# stl_mainboard.net
KiCad netlist of a schematic drawn in EAGLE
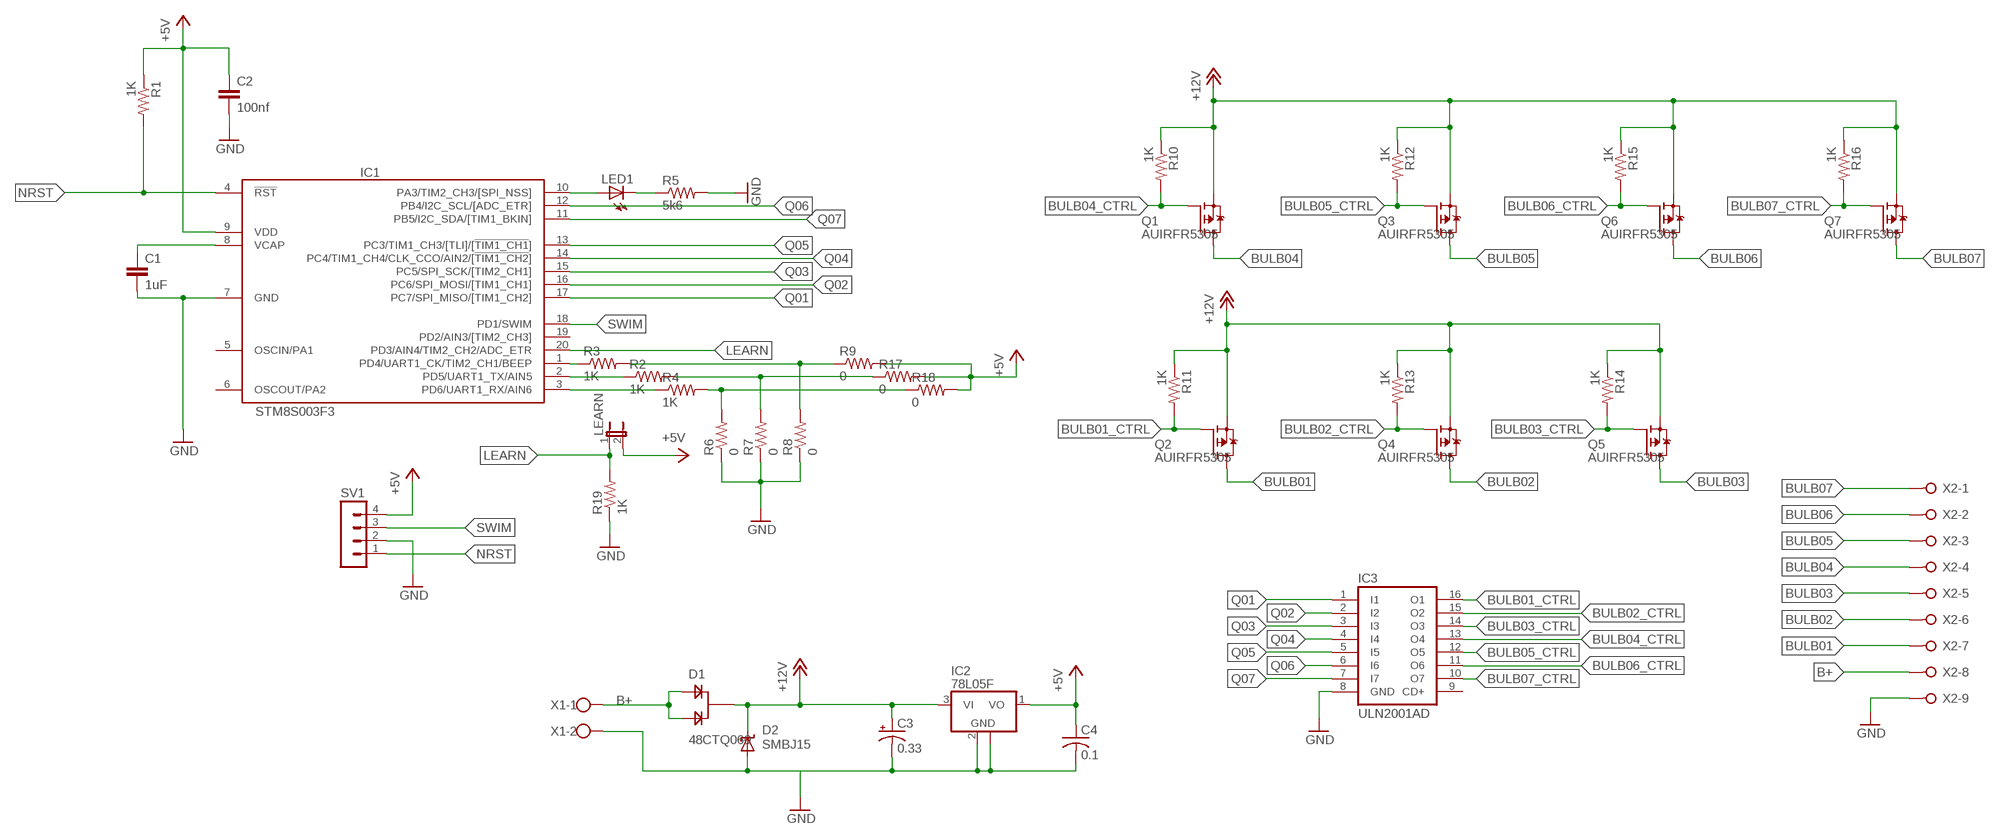
[diagram p0: schematic, sheet 1]

(export (version "E")
  (design (tool "Eeschema 10.0.6"))
  (components
    (comp (ref "C1")
      (value "1uF")
      (footprint "eagle-import:C1206")
      (libsource (lib "eagle-import") (part "C-EUC1206"))
    )
    (comp (ref "C2")
      (value "100nf")
      (footprint "eagle-import:C1206")
      (libsource (lib "eagle-import") (part "C-EUC1206"))
    )
    (comp (ref "C3")
      (value "0.33")
      (footprint "eagle-import:E5-8,5")
      (libsource (lib "eagle-import") (part "CPOL-USE5-8.5"))
    )
    (comp (ref "C4")
      (value "0.1")
      (footprint "eagle-import:C0805")
      (libsource (lib "eagle-import") (part "C-USC0805"))
    )
    (comp (ref "D1")
      (value "48CTQ060")
      (footprint "eagle-import:TO263AB")
      (libsource (lib "eagle-import") (part "48CTQ060"))
    )
    (comp (ref "D2")
      (value "SMBJ15")
      (footprint "eagle-import:SMBJ")
      (libsource (lib "eagle-import") (part "SUPPRESSOR-SMBJ"))
    )
    (comp (ref "IC1")
      (value "STM8S003F3")
      (footprint "eagle-import:TSSOP20")
      (libsource (lib "eagle-import") (part "STM8S003F3"))
    )
    (comp (ref "IC2")
      (value "78L05F")
      (footprint "eagle-import:SOT89")
      (libsource (lib "eagle-import") (part "78LF05"))
    )
    (comp (ref "IC3")
      (value "ULN2001AD")
      (footprint "eagle-import:SO16")
      (libsource (lib "eagle-import") (part "ULN2001AD"))
    )
    (comp (ref "LEARN")
      (value "JP1E")
      (footprint "eagle-import:JP1")
      (libsource (lib "eagle-import") (part "JP1E"))
    )
    (comp (ref "LED1")
      (value "LEDSML1206")
      (footprint "eagle-import:SML1206")
      (libsource (lib "eagle-import") (part "LEDSML1206"))
    )
    (comp (ref "Q1")
      (value "AUIRFR5305")
      (footprint "eagle-import:TO252")
      (libsource (lib "eagle-import") (part "SPD30P06PTO252"))
    )
    (comp (ref "Q2")
      (value "AUIRFR5305")
      (footprint "eagle-import:TO252")
      (libsource (lib "eagle-import") (part "SPD30P06PTO252"))
    )
    (comp (ref "Q3")
      (value "AUIRFR5305")
      (footprint "eagle-import:TO252")
      (libsource (lib "eagle-import") (part "SPD30P06PTO252"))
    )
    (comp (ref "Q4")
      (value "AUIRFR5305")
      (footprint "eagle-import:TO252")
      (libsource (lib "eagle-import") (part "SPD30P06PTO252"))
    )
    (comp (ref "Q5")
      (value "AUIRFR5305")
      (footprint "eagle-import:TO252")
      (libsource (lib "eagle-import") (part "SPD30P06PTO252"))
    )
    (comp (ref "Q6")
      (value "AUIRFR5305")
      (footprint "eagle-import:TO252")
      (libsource (lib "eagle-import") (part "SPD30P06PTO252"))
    )
    (comp (ref "Q7")
      (value "AUIRFR5305")
      (footprint "eagle-import:TO252")
      (libsource (lib "eagle-import") (part "SPD30P06PTO252"))
    )
    (comp (ref "R1")
      (value "1K")
      (footprint "eagle-import:M0805")
      (libsource (lib "eagle-import") (part "R-US_M0805"))
    )
    (comp (ref "R2")
      (value "1K")
      (footprint "eagle-import:M0805")
      (libsource (lib "eagle-import") (part "R-US_M0805"))
    )
    (comp (ref "R3")
      (value "1K")
      (footprint "eagle-import:M0805")
      (libsource (lib "eagle-import") (part "R-US_M0805"))
    )
    (comp (ref "R4")
      (value "1K")
      (footprint "eagle-import:M0805")
      (libsource (lib "eagle-import") (part "R-US_M0805"))
    )
    (comp (ref "R5")
      (value "5k6")
      (footprint "eagle-import:M0805")
      (libsource (lib "eagle-import") (part "R-US_M0805"))
    )
    (comp (ref "R6")
      (value "0")
      (footprint "eagle-import:M0805")
      (libsource (lib "eagle-import") (part "R-US_M0805"))
    )
    (comp (ref "R7")
      (value "0")
      (footprint "eagle-import:M0805")
      (libsource (lib "eagle-import") (part "R-US_M0805"))
    )
    (comp (ref "R8")
      (value "0")
      (footprint "eagle-import:M0805")
      (libsource (lib "eagle-import") (part "R-US_M0805"))
    )
    (comp (ref "R9")
      (value "0")
      (footprint "eagle-import:M0805")
      (libsource (lib "eagle-import") (part "R-US_M0805"))
    )
    (comp (ref "R10")
      (value "1K")
      (footprint "eagle-import:M0805")
      (libsource (lib "eagle-import") (part "R-US_M0805"))
    )
    (comp (ref "R11")
      (value "1K")
      (footprint "eagle-import:M0805")
      (libsource (lib "eagle-import") (part "R-US_M0805"))
    )
    (comp (ref "R12")
      (value "1K")
      (footprint "eagle-import:M0805")
      (libsource (lib "eagle-import") (part "R-US_M0805"))
    )
    (comp (ref "R13")
      (value "1K")
      (footprint "eagle-import:M0805")
      (libsource (lib "eagle-import") (part "R-US_M0805"))
    )
    (comp (ref "R14")
      (value "1K")
      (footprint "eagle-import:M0805")
      (libsource (lib "eagle-import") (part "R-US_M0805"))
    )
    (comp (ref "R15")
      (value "1K")
      (footprint "eagle-import:M0805")
      (libsource (lib "eagle-import") (part "R-US_M0805"))
    )
    (comp (ref "R16")
      (value "1K")
      (footprint "eagle-import:M0805")
      (libsource (lib "eagle-import") (part "R-US_M0805"))
    )
    (comp (ref "R17")
      (value "0")
      (footprint "eagle-import:M0805")
      (libsource (lib "eagle-import") (part "R-US_M0805"))
    )
    (comp (ref "R18")
      (value "0")
      (footprint "eagle-import:M0805")
      (libsource (lib "eagle-import") (part "R-US_M0805"))
    )
    (comp (ref "R19")
      (value "1K")
      (footprint "eagle-import:M0805")
      (libsource (lib "eagle-import") (part "R-US_M0805"))
    )
    (comp (ref "SV1")
      (value "MA04-1")
      (footprint "eagle-import:MA04-1")
      (libsource (lib "eagle-import") (part "MA04-1"))
    )
    (comp (ref "X1")
      (value "W237-102")
      (footprint "eagle-import:W237-102")
      (fields (field (name "MPN") "237-102"))
      (libsource (lib "eagle-import") (part "W237-102"))
    )
    (comp (ref "X2")
      (value "W237-09P")
      (footprint "eagle-import:W237-9P")
      (libsource (lib "eagle-import") (part "W237-09P"))
    )
  )
  (nets
    (net (code "1") (name "+5V") (class "Default")
      (node (ref "C2") (pin "1") (pinfunction "1_1") (pintype "passive"))
      (node (ref "C4") (pin "1") (pinfunction "1_1") (pintype "passive"))
      (node (ref "IC1") (pin "9") (pinfunction "VDD_9") (pintype "power_in"))
      (node (ref "IC2") (pin "1") (pinfunction "VO_1") (pintype "passive"))
      (node (ref "LEARN") (pin "2") (pinfunction "2_2") (pintype "passive"))
      (node (ref "R1") (pin "1") (pinfunction "1_1") (pintype "passive"))
      (node (ref "R17") (pin "2") (pinfunction "2_2") (pintype "passive"))
      (node (ref "R18") (pin "2") (pinfunction "2_2") (pintype "passive"))
      (node (ref "R9") (pin "2") (pinfunction "2_2") (pintype "passive"))
      (node (ref "SV1") (pin "4") (pinfunction "4_4") (pintype "passive"))
    )
    (net (code "2") (name "+12V") (class "Default")
      (node (ref "C3") (pin "+") (pinfunction "+_+") (pintype "passive"))
      (node (ref "D1") (pin "K") (pinfunction "P$1_K") (pintype "bidirectional"))
      (node (ref "D2") (pin "C") (pinfunction "C_C") (pintype "passive"))
      (node (ref "IC2") (pin "3") (pinfunction "VI_3") (pintype "input"))
      (node (ref "Q1") (pin "2") (pinfunction "S_2") (pintype "passive"))
      (node (ref "Q2") (pin "2") (pinfunction "S_2") (pintype "passive"))
      (node (ref "Q3") (pin "2") (pinfunction "S_2") (pintype "passive"))
      (node (ref "Q4") (pin "2") (pinfunction "S_2") (pintype "passive"))
      (node (ref "Q5") (pin "2") (pinfunction "S_2") (pintype "passive"))
      (node (ref "Q6") (pin "2") (pinfunction "S_2") (pintype "passive"))
      (node (ref "Q7") (pin "2") (pinfunction "S_2") (pintype "passive"))
      (node (ref "R10") (pin "1") (pinfunction "1_1") (pintype "passive"))
      (node (ref "R11") (pin "1") (pinfunction "1_1") (pintype "passive"))
      (node (ref "R12") (pin "1") (pinfunction "1_1") (pintype "passive"))
      (node (ref "R13") (pin "1") (pinfunction "1_1") (pintype "passive"))
      (node (ref "R14") (pin "1") (pinfunction "1_1") (pintype "passive"))
      (node (ref "R15") (pin "1") (pinfunction "1_1") (pintype "passive"))
      (node (ref "R16") (pin "1") (pinfunction "1_1") (pintype "passive"))
    )
    (net (code "3") (name "B+") (class "Default")
      (node (ref "D1") (pin "1") (pinfunction "P$2_1") (pintype "bidirectional"))
      (node (ref "D1") (pin "2") (pinfunction "P$3_2") (pintype "bidirectional"))
      (node (ref "X1") (pin "1") (pinfunction "KL_1") (pintype "passive"))
      (node (ref "X2") (pin "8") (pinfunction "KL_8") (pintype "passive"))
    )
    (net (code "4") (name "BULB01") (class "Default")
      (node (ref "Q2") (pin "3") (pinfunction "D_3") (pintype "passive"))
      (node (ref "X2") (pin "7") (pinfunction "KL_7") (pintype "passive"))
    )
    (net (code "5") (name "BULB01_CTRL") (class "Default")
      (node (ref "IC3") (pin "16") (pinfunction "O1_16") (pintype "open_collector"))
      (node (ref "Q2") (pin "1") (pinfunction "G_1") (pintype "passive"))
      (node (ref "R11") (pin "2") (pinfunction "2_2") (pintype "passive"))
    )
    (net (code "6") (name "BULB02") (class "Default")
      (node (ref "Q4") (pin "3") (pinfunction "D_3") (pintype "passive"))
      (node (ref "X2") (pin "6") (pinfunction "KL_6") (pintype "passive"))
    )
    (net (code "7") (name "BULB02_CTRL") (class "Default")
      (node (ref "IC3") (pin "15") (pinfunction "O2_15") (pintype "open_collector"))
      (node (ref "Q4") (pin "1") (pinfunction "G_1") (pintype "passive"))
      (node (ref "R13") (pin "2") (pinfunction "2_2") (pintype "passive"))
    )
    (net (code "8") (name "BULB03") (class "Default")
      (node (ref "Q5") (pin "3") (pinfunction "D_3") (pintype "passive"))
      (node (ref "X2") (pin "5") (pinfunction "KL_5") (pintype "passive"))
    )
    (net (code "9") (name "BULB03_CTRL") (class "Default")
      (node (ref "IC3") (pin "14") (pinfunction "O3_14") (pintype "open_collector"))
      (node (ref "Q5") (pin "1") (pinfunction "G_1") (pintype "passive"))
      (node (ref "R14") (pin "2") (pinfunction "2_2") (pintype "passive"))
    )
    (net (code "10") (name "BULB04") (class "Default")
      (node (ref "Q1") (pin "3") (pinfunction "D_3") (pintype "passive"))
      (node (ref "X2") (pin "4") (pinfunction "KL_4") (pintype "passive"))
    )
    (net (code "11") (name "BULB04_CTRL") (class "Default")
      (node (ref "IC3") (pin "13") (pinfunction "O4_13") (pintype "open_collector"))
      (node (ref "Q1") (pin "1") (pinfunction "G_1") (pintype "passive"))
      (node (ref "R10") (pin "2") (pinfunction "2_2") (pintype "passive"))
    )
    (net (code "12") (name "BULB05") (class "Default")
      (node (ref "Q3") (pin "3") (pinfunction "D_3") (pintype "passive"))
      (node (ref "X2") (pin "3") (pinfunction "KL_3") (pintype "passive"))
    )
    (net (code "13") (name "BULB05_CTRL") (class "Default")
      (node (ref "IC3") (pin "12") (pinfunction "O5_12") (pintype "open_collector"))
      (node (ref "Q3") (pin "1") (pinfunction "G_1") (pintype "passive"))
      (node (ref "R12") (pin "2") (pinfunction "2_2") (pintype "passive"))
    )
    (net (code "14") (name "BULB06") (class "Default")
      (node (ref "Q6") (pin "3") (pinfunction "D_3") (pintype "passive"))
      (node (ref "X2") (pin "2") (pinfunction "KL_2") (pintype "passive"))
    )
    (net (code "15") (name "BULB06_CTRL") (class "Default")
      (node (ref "IC3") (pin "11") (pinfunction "O6_11") (pintype "open_collector"))
      (node (ref "Q6") (pin "1") (pinfunction "G_1") (pintype "passive"))
      (node (ref "R15") (pin "2") (pinfunction "2_2") (pintype "passive"))
    )
    (net (code "16") (name "BULB07") (class "Default")
      (node (ref "Q7") (pin "3") (pinfunction "D_3") (pintype "passive"))
      (node (ref "X2") (pin "1") (pinfunction "KL_1") (pintype "passive"))
    )
    (net (code "17") (name "BULB07_CTRL") (class "Default")
      (node (ref "IC3") (pin "10") (pinfunction "O7_10") (pintype "open_collector"))
      (node (ref "Q7") (pin "1") (pinfunction "G_1") (pintype "passive"))
      (node (ref "R16") (pin "2") (pinfunction "2_2") (pintype "passive"))
    )
    (net (code "18") (name "GND") (class "Default")
      (node (ref "C1") (pin "2") (pinfunction "2_2") (pintype "passive"))
      (node (ref "C2") (pin "2") (pinfunction "2_2") (pintype "passive"))
      (node (ref "C3") (pin "-") (pinfunction "-_-") (pintype "passive"))
      (node (ref "C4") (pin "2") (pinfunction "2_2") (pintype "passive"))
      (node (ref "D2") (pin "A") (pinfunction "A_A") (pintype "passive"))
      (node (ref "IC1") (pin "7") (pinfunction "GND_7") (pintype "power_in"))
      (node (ref "IC2") (pin "2") (pinfunction "GND_2") (pintype "passive"))
      (node (ref "IC2") (pin "2@1") (pinfunction "GND_2@1") (pintype "passive"))
      (node (ref "IC3") (pin "8") (pinfunction "GND_8") (pintype "power_in"))
      (node (ref "R19") (pin "1") (pinfunction "1_1") (pintype "passive"))
      (node (ref "R5") (pin "2") (pinfunction "2_2") (pintype "passive"))
      (node (ref "R6") (pin "1") (pinfunction "1_1") (pintype "passive"))
      (node (ref "R7") (pin "1") (pinfunction "1_1") (pintype "passive"))
      (node (ref "R8") (pin "1") (pinfunction "1_1") (pintype "passive"))
      (node (ref "SV1") (pin "2") (pinfunction "2_2") (pintype "passive"))
      (node (ref "X1") (pin "2") (pinfunction "KL_2") (pintype "passive"))
      (node (ref "X2") (pin "9") (pinfunction "KL_9") (pintype "passive"))
    )
    (net (code "19") (name "LEARN") (class "Default")
      (node (ref "IC1") (pin "20") (pinfunction "PD3/AIN4/TIM2_CH2/ADC_ETR_20") (pintype "bidirectional"))
      (node (ref "LEARN") (pin "1") (pinfunction "1_1") (pintype "passive"))
      (node (ref "R19") (pin "2") (pinfunction "2_2") (pintype "passive"))
    )
    (net (code "20") (name "NRST") (class "Default")
      (node (ref "IC1") (pin "4") (pinfunction "~{RST}_4") (pintype "input"))
      (node (ref "R1") (pin "2") (pinfunction "2_2") (pintype "passive"))
      (node (ref "SV1") (pin "1") (pinfunction "1_1") (pintype "passive"))
    )
    (net (code "21") (name "Net-(IC1-PA3{slash}TIM2_CH3{slash}[SPI_NSS])") (class "Default")
      (node (ref "IC1") (pin "10") (pinfunction "PA3/TIM2_CH3/[SPI_NSS]_10") (pintype "bidirectional"))
      (node (ref "LED1") (pin "A") (pinfunction "A_A") (pintype "passive"))
    )
    (net (code "22") (name "Net-(IC1-PD4{slash}UART1_CK{slash}TIM2_CH1{slash}BEEP)") (class "Default")
      (node (ref "IC1") (pin "1") (pinfunction "PD4/UART1_CK/TIM2_CH1/BEEP_1") (pintype "bidirectional"))
      (node (ref "R3") (pin "1") (pinfunction "1_1") (pintype "passive"))
    )
    (net (code "23") (name "Net-(IC1-PD5{slash}UART1_TX{slash}AIN5)") (class "Default")
      (node (ref "IC1") (pin "2") (pinfunction "PD5/UART1_TX/AIN5_2") (pintype "bidirectional"))
      (node (ref "R2") (pin "1") (pinfunction "1_1") (pintype "passive"))
    )
    (net (code "24") (name "Net-(IC1-PD6{slash}UART1_RX{slash}AIN6)") (class "Default")
      (node (ref "IC1") (pin "3") (pinfunction "PD6/UART1_RX/AIN6_3") (pintype "bidirectional"))
      (node (ref "R4") (pin "1") (pinfunction "1_1") (pintype "passive"))
    )
    (net (code "25") (name "Net-(IC1-VCAP)") (class "Default")
      (node (ref "C1") (pin "1") (pinfunction "1_1") (pintype "passive"))
      (node (ref "IC1") (pin "8") (pinfunction "VCAP_8") (pintype "power_in"))
    )
    (net (code "26") (name "Net-(LED1-PadC)") (class "Default")
      (node (ref "LED1") (pin "C") (pinfunction "C_C") (pintype "passive"))
      (node (ref "R5") (pin "1") (pinfunction "1_1") (pintype "passive"))
    )
    (net (code "27") (name "Net-(R3-Pad2)") (class "Default")
      (node (ref "R3") (pin "2") (pinfunction "2_2") (pintype "passive"))
      (node (ref "R8") (pin "2") (pinfunction "2_2") (pintype "passive"))
      (node (ref "R9") (pin "1") (pinfunction "1_1") (pintype "passive"))
    )
    (net (code "28") (name "Net-(R17-Pad1)") (class "Default")
      (node (ref "R17") (pin "1") (pinfunction "1_1") (pintype "passive"))
      (node (ref "R2") (pin "2") (pinfunction "2_2") (pintype "passive"))
      (node (ref "R7") (pin "2") (pinfunction "2_2") (pintype "passive"))
    )
    (net (code "29") (name "Net-(R18-Pad1)") (class "Default")
      (node (ref "R18") (pin "1") (pinfunction "1_1") (pintype "passive"))
      (node (ref "R4") (pin "2") (pinfunction "2_2") (pintype "passive"))
      (node (ref "R6") (pin "2") (pinfunction "2_2") (pintype "passive"))
    )
    (net (code "30") (name "Q01") (class "Default")
      (node (ref "IC1") (pin "17") (pinfunction "PC7/SPI_MISO/[TIM1_CH2]_17") (pintype "bidirectional"))
      (node (ref "IC3") (pin "1") (pinfunction "I1_1") (pintype "input"))
    )
    (net (code "31") (name "Q02") (class "Default")
      (node (ref "IC1") (pin "16") (pinfunction "PC6/SPI_MOSI/[TIM1_CH1]_16") (pintype "bidirectional"))
      (node (ref "IC3") (pin "2") (pinfunction "I2_2") (pintype "input"))
    )
    (net (code "32") (name "Q03") (class "Default")
      (node (ref "IC1") (pin "15") (pinfunction "PC5/SPI_SCK/[TIM2_CH1]_15") (pintype "bidirectional"))
      (node (ref "IC3") (pin "3") (pinfunction "I3_3") (pintype "input"))
    )
    (net (code "33") (name "Q04") (class "Default")
      (node (ref "IC1") (pin "14") (pinfunction "PC4/TIM1_CH4/CLK_CCO/AIN2/[~{TIM1_CH2}]_14") (pintype "bidirectional"))
      (node (ref "IC3") (pin "4") (pinfunction "I4_4") (pintype "input"))
    )
    (net (code "34") (name "Q05") (class "Default")
      (node (ref "IC1") (pin "13") (pinfunction "PC3/TIM1_CH3/[TLI]/[~{TIM1_CH1}]_13") (pintype "bidirectional"))
      (node (ref "IC3") (pin "5") (pinfunction "I5_5") (pintype "input"))
    )
    (net (code "35") (name "Q06") (class "Default")
      (node (ref "IC1") (pin "12") (pinfunction "PB4/I2C_SCL/[ADC_ETR]_12") (pintype "bidirectional"))
      (node (ref "IC3") (pin "6") (pinfunction "I6_6") (pintype "input"))
    )
    (net (code "36") (name "Q07") (class "Default")
      (node (ref "IC1") (pin "11") (pinfunction "PB5/I2C_SDA/[TIM1_BKIN]_11") (pintype "bidirectional"))
      (node (ref "IC3") (pin "7") (pinfunction "I7_7") (pintype "input"))
    )
    (net (code "37") (name "SWIM") (class "Default")
      (node (ref "IC1") (pin "18") (pinfunction "PD1/SWIM_18") (pintype "bidirectional"))
      (node (ref "SV1") (pin "3") (pinfunction "3_3") (pintype "passive"))
    )
    (net (code "38") (name "unconnected-(IC1-OSCIN{slash}PA1-Pad5)") (class "Default")
      (node (ref "IC1") (pin "5") (pinfunction "OSCIN/PA1_5") (pintype "bidirectional"))
    )
    (net (code "39") (name "unconnected-(IC1-OSCOUT{slash}PA2-Pad6)") (class "Default")
      (node (ref "IC1") (pin "6") (pinfunction "OSCOUT/PA2_6") (pintype "bidirectional"))
    )
    (net (code "40") (name "unconnected-(IC1-PD2{slash}AIN3{slash}[TIM2_CH3]-Pad19)") (class "Default")
      (node (ref "IC1") (pin "19") (pinfunction "PD2/AIN3/[TIM2_CH3]_19") (pintype "bidirectional"))
    )
    (net (code "41") (name "unconnected-(IC3-CD+-Pad9)") (class "Default")
      (node (ref "IC3") (pin "9") (pinfunction "CD+_9") (pintype "passive"))
    )
  )
)
